# blinky.net
KiCad netlist of a schematic drawn in EAGLE
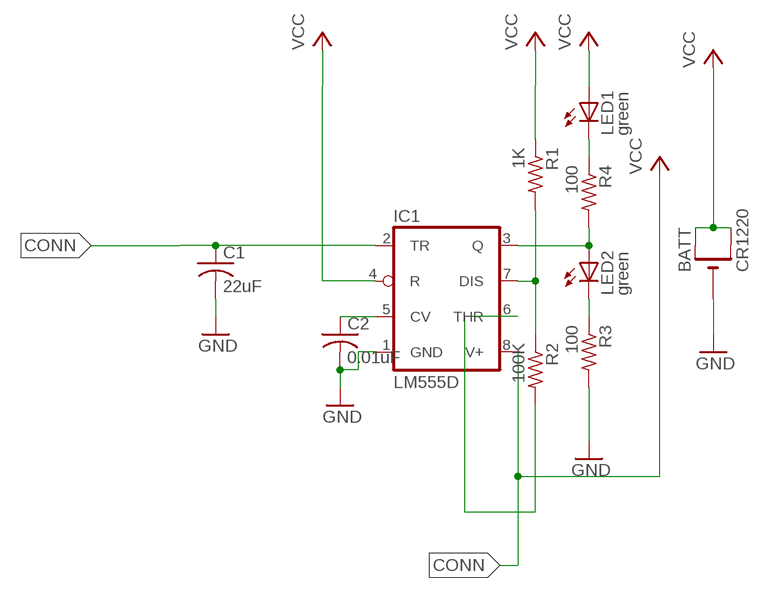
[diagram p0: schematic, sheet 1]

(export (version "E")
  (design (tool "Eeschema 10.0.6"))
  (components
    (comp (ref "BATT")
      (value "CR1220")
      (footprint "eagle-import:CR1220-SMD")
      (fields (field (name "MF") "KEYSTONE ELECTR") (field (name "MPN") "3000"))
      (libsource (lib "eagle-import") (part "CR1220SMT"))
    )
    (comp (ref "C1")
      (value "22uF")
      (footprint "eagle-import:C0805")
      (fields (field (name "MPN") "NOJA226M006RWJ"))
      (libsource (lib "eagle-import") (part "C-USC0805"))
    )
    (comp (ref "C2")
      (value "0.01uF")
      (footprint "eagle-import:C0805")
      (fields (field (name "MPN") "B32529C103K"))
      (libsource (lib "eagle-import") (part "C-USC0805"))
    )
    (comp (ref "IC1")
      (value "LM555D")
      (footprint "eagle-import:SO08")
      (libsource (lib "eagle-import") (part "555DLM"))
    )
    (comp (ref "LED1")
      (value "green")
      (footprint "eagle-import:CHIP-LED0805")
      (fields (field (name "MF") "DIALIGHT") (field (name "MPN") "551-0207F"))
      (libsource (lib "eagle-import") (part "LEDCHIP-LED0805"))
    )
    (comp (ref "LED2")
      (value "green")
      (footprint "eagle-import:CHIP-LED0805")
      (fields (field (name "MF") "DIALIGHT") (field (name "MPN") "551-0207F"))
      (libsource (lib "eagle-import") (part "LEDCHIP-LED0805"))
    )
    (comp (ref "R1")
      (value "1K")
      (footprint "eagle-import:M0805")
      (fields (field (name "MF") "FARNELL") (field (name "MPN") "MCF 0.25W 1K"))
      (libsource (lib "eagle-import") (part "R-US_M0805"))
    )
    (comp (ref "R2")
      (value "100K")
      (footprint "eagle-import:M0805")
      (fields (field (name "MPN") "RC0402FR-13100KL"))
      (libsource (lib "eagle-import") (part "R-US_M0805"))
    )
    (comp (ref "R3")
      (value "100")
      (footprint "eagle-import:M0805")
      (fields (field (name "MPN") "04025C332KAT2A"))
      (libsource (lib "eagle-import") (part "R-US_M0805"))
    )
    (comp (ref "R4")
      (value "100")
      (footprint "eagle-import:M0805")
      (fields (field (name "MPN") "04025C332KAT2A"))
      (libsource (lib "eagle-import") (part "R-US_M0805"))
    )
  )
  (nets
    (net (code "1") (name "CONN") (class "Default")
      (node (ref "C1") (pin "1") (pinfunction "1_1") (pintype "passive"))
      (node (ref "IC1") (pin "2") (pinfunction "TR_2") (pintype "input"))
    )
    (net (code "2") (name "GND") (class "Default")
      (node (ref "BATT") (pin "-") (pinfunction "-_-") (pintype "passive"))
      (node (ref "C1") (pin "2") (pinfunction "2_2") (pintype "passive"))
      (node (ref "C2") (pin "2") (pinfunction "2_2") (pintype "passive"))
      (node (ref "IC1") (pin "1") (pinfunction "GND_1") (pintype "power_in"))
      (node (ref "R3") (pin "2") (pinfunction "2_2") (pintype "passive"))
    )
    (net (code "3") (name "Net-(IC1-CV)") (class "Default")
      (node (ref "C2") (pin "1") (pinfunction "1_1") (pintype "passive"))
      (node (ref "IC1") (pin "5") (pinfunction "CV_5") (pintype "input"))
    )
    (net (code "4") (name "Net-(IC1-DIS)") (class "Default")
      (node (ref "IC1") (pin "7") (pinfunction "DIS_7") (pintype "input"))
      (node (ref "R1") (pin "2") (pinfunction "2_2") (pintype "passive"))
      (node (ref "R2") (pin "1") (pinfunction "1_1") (pintype "passive"))
    )
    (net (code "5") (name "Net-(IC1-Q)") (class "Default")
      (node (ref "IC1") (pin "3") (pinfunction "Q_3") (pintype "output"))
      (node (ref "LED2") (pin "A") (pinfunction "A_A") (pintype "passive"))
      (node (ref "R4") (pin "2") (pinfunction "2_2") (pintype "passive"))
    )
    (net (code "6") (name "Net-(IC1-THR)") (class "Default")
      (node (ref "IC1") (pin "6") (pinfunction "THR_6") (pintype "input"))
      (node (ref "R2") (pin "2") (pinfunction "2_2") (pintype "passive"))
    )
    (net (code "7") (name "Net-(LED1-PadC)") (class "Default")
      (node (ref "LED1") (pin "C") (pinfunction "C_C") (pintype "passive"))
      (node (ref "R4") (pin "1") (pinfunction "1_1") (pintype "passive"))
    )
    (net (code "8") (name "Net-(LED2-PadC)") (class "Default")
      (node (ref "LED2") (pin "C") (pinfunction "C_C") (pintype "passive"))
      (node (ref "R3") (pin "1") (pinfunction "1_1") (pintype "passive"))
    )
    (net (code "9") (name "VCC") (class "Default")
      (node (ref "BATT") (pin "+$1") (pinfunction "+_+$1") (pintype "passive"))
      (node (ref "BATT") (pin "+$2") (pinfunction "+1_+$2") (pintype "passive"))
      (node (ref "IC1") (pin "4") (pinfunction "R_4") (pintype "input"))
      (node (ref "IC1") (pin "8") (pinfunction "V+_8") (pintype "power_in"))
      (node (ref "LED1") (pin "A") (pinfunction "A_A") (pintype "passive"))
      (node (ref "R1") (pin "1") (pinfunction "1_1") (pintype "passive"))
    )
  )
)
